# tachometerMv1.net
KiCad netlist of a schematic drawn in EAGLE
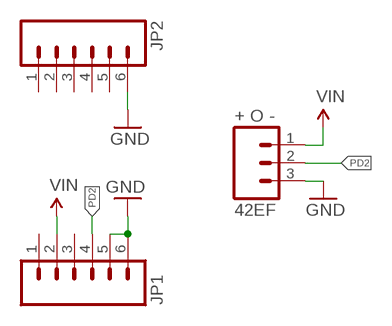
[diagram p0: schematic, sheet 1]

(export (version "E")
  (design (tool "Eeschema 10.0.6"))
  (components
    (comp (ref "42EF")
      (value "+ O -")
      (footprint "eagle-import:1X03_LOCK_LONGPADS")
      (libsource (lib "eagle-import") (part "M03LOCK_LONGPADS"))
    )
    (comp (ref "JP1")
      (value "M06LOCK_LONGPADS")
      (footprint "eagle-import:1X06_LOCK_LONGPADS")
      (libsource (lib "eagle-import") (part "M06LOCK_LONGPADS"))
    )
    (comp (ref "JP2")
      (value "M06LOCK_LONGPADS")
      (footprint "eagle-import:1X06_LOCK_LONGPADS")
      (libsource (lib "eagle-import") (part "M06LOCK_LONGPADS"))
    )
  )
  (nets
    (net (code "1") (name "GND") (class "Default")
      (node (ref "42EF") (pin "3") (pinfunction "3_3") (pintype "passive"))
      (node (ref "JP1") (pin "5") (pinfunction "5_5") (pintype "passive"))
      (node (ref "JP1") (pin "6") (pinfunction "6_6") (pintype "passive"))
      (node (ref "JP2") (pin "6") (pinfunction "6_6") (pintype "passive"))
    )
    (net (code "2") (name "PD2") (class "Default")
      (node (ref "42EF") (pin "2") (pinfunction "2_2") (pintype "passive"))
      (node (ref "JP1") (pin "4") (pinfunction "4_4") (pintype "passive"))
    )
    (net (code "3") (name "VIN") (class "Default")
      (node (ref "42EF") (pin "1") (pinfunction "1_1") (pintype "passive"))
      (node (ref "JP1") (pin "2") (pinfunction "2_2") (pintype "passive"))
    )
    (net (code "4") (name "unconnected-(JP1-Pad1)") (class "Default")
      (node (ref "JP1") (pin "1") (pinfunction "1_1") (pintype "passive"))
    )
    (net (code "5") (name "unconnected-(JP1-Pad3)") (class "Default")
      (node (ref "JP1") (pin "3") (pinfunction "3_3") (pintype "passive"))
    )
    (net (code "6") (name "unconnected-(JP2-Pad1)") (class "Default")
      (node (ref "JP2") (pin "1") (pinfunction "1_1") (pintype "passive"))
    )
    (net (code "7") (name "unconnected-(JP2-Pad2)") (class "Default")
      (node (ref "JP2") (pin "2") (pinfunction "2_2") (pintype "passive"))
    )
    (net (code "8") (name "unconnected-(JP2-Pad3)") (class "Default")
      (node (ref "JP2") (pin "3") (pinfunction "3_3") (pintype "passive"))
    )
    (net (code "9") (name "unconnected-(JP2-Pad4)") (class "Default")
      (node (ref "JP2") (pin "4") (pinfunction "4_4") (pintype "passive"))
    )
    (net (code "10") (name "unconnected-(JP2-Pad5)") (class "Default")
      (node (ref "JP2") (pin "5") (pinfunction "5_5") (pintype "passive"))
    )
  )
)
